# Thrusters.net
KiCad netlist of a schematic drawn in Altium Designer
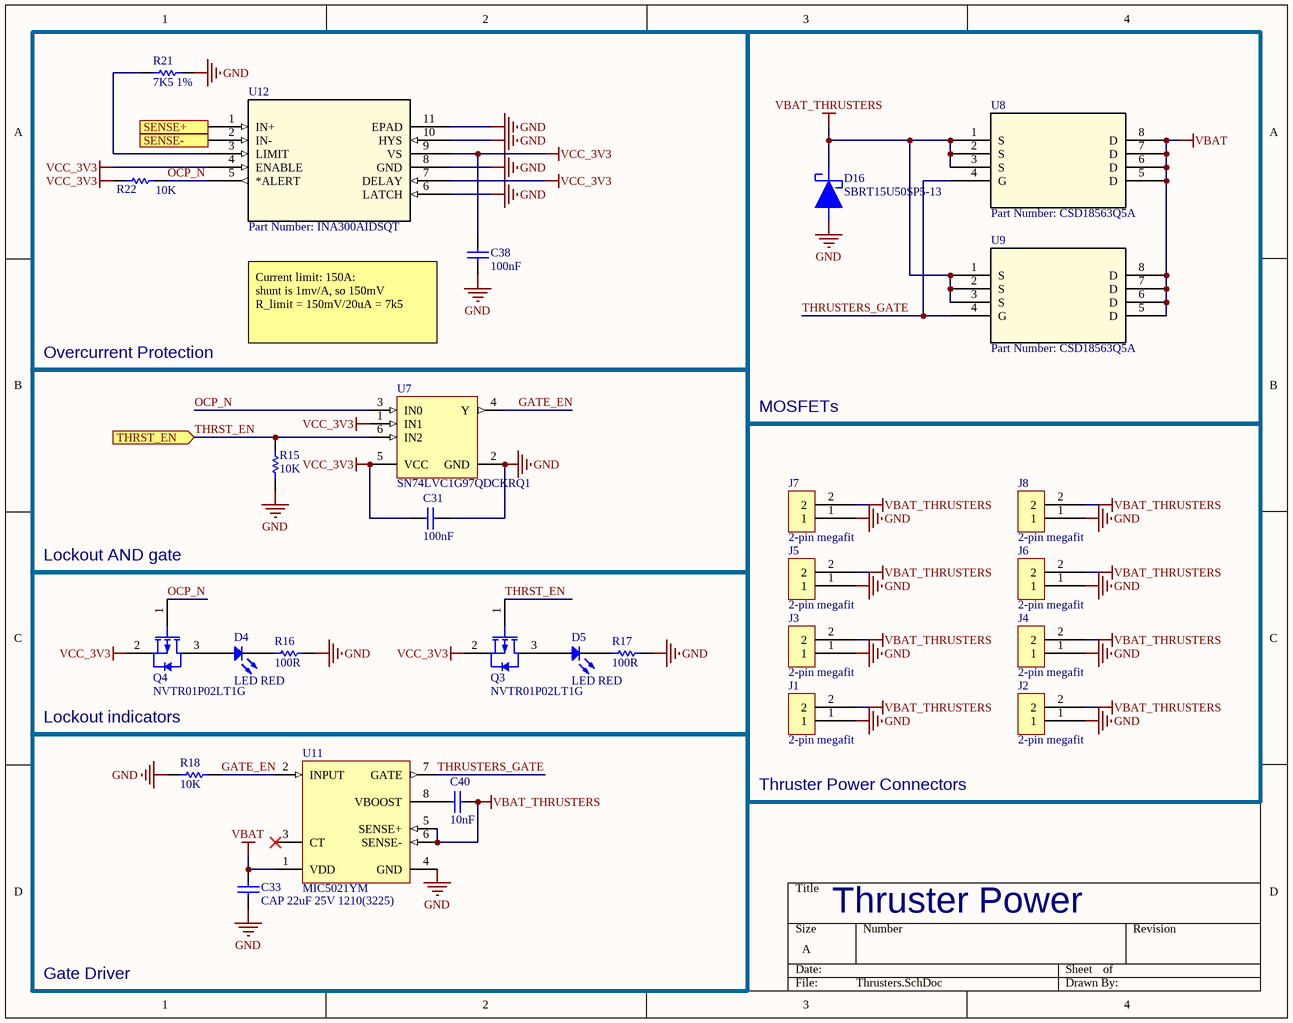
[diagram p0: Thrusters.SchDoc]

(export (version "E")
  (design (tool "Eeschema 10.0.6"))
  (components
    (comp (ref "C31")
      (value "100nF")
      (footprint "CAPC0603(1608)100_N")
      (description "CAP 100nF 10V ±10% 0603 (1608 Metric) Thickness 1mm SMD")
      (fields (field (name "TOLERANCE") "Â±10%"))
      (libsource (lib "Altium Content Vault") (part "CAP"))
    )
    (comp (ref "C33")
      (value "CAP 22uF 25V 1210(3225)")
      (footprint "CAPC1210(3225)220_L")
      (description "CAP 22uF 25V -20% to +80% 1210 (3225 Metric) Thickness 2.2mm SMD")
      (fields (field (name "TOLERANCE") "-20% to +80%"))
      (libsource (lib "Altium Content Vault") (part "CAP"))
    )
    (comp (ref "C38")
      (value "100nF")
      (footprint "CAPC0603(1608)100_N")
      (description "CAP 100nF 10V ±10% 0603 (1608 Metric) Thickness 1mm SMD")
      (fields (field (name "TOLERANCE") "Â±10%"))
      (libsource (lib "Altium Content Vault") (part "CAP"))
    )
    (comp (ref "C40")
      (value "10nF")
      (footprint "CAPC0603(1608)100_L")
      (description "CAP 10nF 25V ±2% 0603 (1608 Metric) Thickness 1mm SMD")
      (fields (field (name "TOLERANCE") "Â±2%"))
      (libsource (lib "Altium Content Vault") (part "CAP"))
    )
    (comp (ref "D4")
      (value "LED RED")
      (footprint "LED_0805")
      (description "led\r\n LTST-C171KRKT")
      (fields
        (field (name "MANUFACTURER") "Lite-On Inc.")
        (field (name "MANUFACTURER PART NUMBER") "LTST-C171KRKT")
      )
      (libsource (lib "CMR_Miscellaneous_Devices") (part "LED0"))
    )
    (comp (ref "D5")
      (value "LED RED")
      (footprint "LED_0805")
      (description "led\r\n LTST-C171KRKT")
      (fields
        (field (name "MANUFACTURER") "Lite-On Inc.")
        (field (name "MANUFACTURER PART NUMBER") "LTST-C171KRKT")
      )
      (libsource (lib "CMR_Miscellaneous_Devices") (part "LED0"))
    )
    (comp (ref "D16")
      (value "SBRT15U50SP5-13")
      (footprint "SBRT15U50SP5-13")
      (fields (field (name "MANUFACTURER") "Diodes Incorporated"))
      (libsource (lib "CMR_Miscellaneous_Devices") (part "SBRT15U50SP5-13"))
    )
    (comp (ref "J1")
      (value "2-pin megafit")
      (footprint "2-pin Megafit RA")
      (libsource (lib "Tauv-Lib") (part "2-pin megafit"))
    )
    (comp (ref "J2")
      (value "2-pin megafit")
      (footprint "2-pin Megafit RA")
      (libsource (lib "Tauv-Lib") (part "2-pin megafit"))
    )
    (comp (ref "J3")
      (value "2-pin megafit")
      (footprint "2-pin Megafit RA")
      (libsource (lib "Tauv-Lib") (part "2-pin megafit"))
    )
    (comp (ref "J4")
      (value "2-pin megafit")
      (footprint "2-pin Megafit RA")
      (libsource (lib "Tauv-Lib") (part "2-pin megafit"))
    )
    (comp (ref "J5")
      (value "2-pin megafit")
      (footprint "2-pin Megafit RA")
      (libsource (lib "Tauv-Lib") (part "2-pin megafit"))
    )
    (comp (ref "J6")
      (value "2-pin megafit")
      (footprint "2-pin Megafit RA")
      (libsource (lib "Tauv-Lib") (part "2-pin megafit"))
    )
    (comp (ref "J7")
      (value "2-pin megafit")
      (footprint "2-pin Megafit RA")
      (libsource (lib "Tauv-Lib") (part "2-pin megafit"))
    )
    (comp (ref "J8")
      (value "2-pin megafit")
      (footprint "2-pin Megafit RA")
      (libsource (lib "Tauv-Lib") (part "2-pin megafit"))
    )
    (comp (ref "Q3")
      (value "NVTR01P02LT1G")
      (footprint "ONSC-SOT-23-3-318-08_V")
      (description "Power MOSFET, -20 V, -1.3 A, P-Channel, 3-Pin SOT-23, Pb-Free, Tape and Reel")
      (fields (field (name "MANUFACTURER") "On Semiconductor"))
      (libsource (lib "Altium Content Vault") (part "ONSC-PMOS-G1S2D3-3_D"))
    )
    (comp (ref "Q4")
      (value "NVTR01P02LT1G")
      (footprint "ONSC-SOT-23-3-318-08_V")
      (description "Power MOSFET, -20 V, -1.3 A, P-Channel, 3-Pin SOT-23, Pb-Free, Tape and Reel")
      (fields (field (name "MANUFACTURER") "On Semiconductor"))
      (libsource (lib "Altium Content Vault") (part "ONSC-PMOS-G1S2D3-3_D"))
    )
    (comp (ref "R15")
      (value "10K")
      (footprint "RESC0603(1608)_N")
      (description "10K 0.1W 5% 0603 (1608 Metric)  SMD")
      (fields (field (name "TOLERANCE") "5 %") (field (name "POWER") "0.1 W"))
      (libsource (lib "Altium Content Vault") (part "RES"))
    )
    (comp (ref "R16")
      (value "100R")
      (footprint "RESC0603(1608)_N")
      (description "100R 0.1W 5% 0603 (1608 Metric)  SMD")
      (fields (field (name "TOLERANCE") "5 %") (field (name "POWER") "0.1 W"))
      (libsource (lib "Altium Content Vault") (part "RES"))
    )
    (comp (ref "R17")
      (value "100R")
      (footprint "RESC0603(1608)_N")
      (description "100R 0.1W 5% 0603 (1608 Metric)  SMD")
      (fields (field (name "TOLERANCE") "5 %") (field (name "POWER") "0.1 W"))
      (libsource (lib "Altium Content Vault") (part "RES"))
    )
    (comp (ref "R18")
      (value "10K")
      (footprint "RESC0603(1608)_N")
      (description "10K 0.1W 5% 0603 (1608 Metric)  SMD")
      (fields (field (name "TOLERANCE") "5 %") (field (name "POWER") "0.1 W"))
      (libsource (lib "Altium Content Vault") (part "RES"))
    )
    (comp (ref "R21")
      (value "7K5 1%")
      (footprint "RESC0603(1608)_N")
      (description "7K5 0.1W 1% 0603 (1608 Metric)  SMD")
      (fields (field (name "TOLERANCE") "1 %") (field (name "POWER") "0.1 W"))
      (libsource (lib "Altium Content Vault") (part "RES"))
    )
    (comp (ref "R22")
      (value "10K")
      (footprint "RESC0603(1608)_N")
      (description "10K 0.1W 5% 0603 (1608 Metric)  SMD")
      (fields (field (name "TOLERANCE") "5 %") (field (name "POWER") "0.1 W"))
      (libsource (lib "Altium Content Vault") (part "RES"))
    )
    (comp (ref "U7")
      (value "SN74LVC1G97QDCKRQ1")
      (footprint "DCK0006A_L")
      (description "Automotive Catalog Configurable Multiple-Function Gate, DCK0006A, LARGE T&R")
      (fields
        (field (name "MANUFACTURER") "Texas Instruments")
        (field (name "GENERIC PART NUMBER") "SN74LVC1G97-Q1")
      )
      (libsource (lib "Altium Content Vault") (part "TI-SN74XXX1GXX-6"))
    )
    (comp (ref "U8")
      (value "Part Number: CSD18563Q5A")
      (footprint "DQJ8")
      (description "No Description Available")
      (fields
        (field (name "MANUFACTURER_PART_NUMBER") "CSD18563Q5A")
        (field (name "COPYRIGHT") "Copyright (C) 2018 Accelerated Designs. All rights reserved")
      )
      (libsource (lib "Tauv-Lib") (part "CSD18563Q5A"))
    )
    (comp (ref "U9")
      (value "Part Number: CSD18563Q5A")
      (footprint "DQJ8")
      (description "No Description Available")
      (fields
        (field (name "MANUFACTURER_PART_NUMBER") "CSD18563Q5A")
        (field (name "COPYRIGHT") "Copyright (C) 2018 Accelerated Designs. All rights reserved")
      )
      (libsource (lib "Tauv-Lib") (part "CSD18563Q5A"))
    )
    (comp (ref "U11")
      (value "MIC5021YM")
      (footprint "MICL-SOICN-8LD-PL-1_V")
      (description "High-Speed High-Side MOSFET Driver, 12 to 36 V, -40 to 85 degC, 8-Pin SOIC, RoHS, Tube")
      (libsource (lib "Altium Content Vault") (part "MICL-MIC5021B_YM-8"))
    )
    (comp (ref "U12")
      (value "Part Number: INA300AIDSQT")
      (footprint "DSQ10_P9X1P5")
      (description "No Description Available")
      (fields
        (field (name "MANUFACTURER_PART_NUMBER") "INA300AIDSQT")
        (field (name "COPYRIGHT") "Copyright (C) 2018 Accelerated Designs. All rights reserved")
      )
      (libsource (lib "Tauv-Lib") (part "INA300AIDSQT"))
    )
  )
  (nets
    (net (code "1") (name "/GATE_EN") (class "Default")
      (node (ref "R18") (pin "1") (pinfunction "1_1") (pintype "passive"))
      (node (ref "U11") (pin "2") (pinfunction "INPUT_2") (pintype "input"))
      (node (ref "U7") (pin "4") (pinfunction "Y_4") (pintype "output"))
    )
    (net (code "2") (name "/OCP_N") (class "Default")
      (node (ref "Q4") (pin "1") (pinfunction "G_1") (pintype "passive"))
      (node (ref "R22") (pin "1") (pinfunction "1_1") (pintype "passive"))
      (node (ref "U12") (pin "5") (pinfunction "*ALERT_5") (pintype "output"))
      (node (ref "U7") (pin "3") (pinfunction "IN0_3") (pintype "input"))
    )
    (net (code "3") (name "/SENSE+") (class "Default")
      (node (ref "U12") (pin "1") (pinfunction "IN+_1") (pintype "input"))
    )
    (net (code "4") (name "/SENSE-") (class "Default")
      (node (ref "U12") (pin "2") (pinfunction "IN-_2") (pintype "input"))
    )
    (net (code "5") (name "/THRST_EN") (class "Default")
      (node (ref "Q3") (pin "1") (pinfunction "G_1") (pintype "passive"))
      (node (ref "R15") (pin "1") (pinfunction "1_1") (pintype "passive"))
      (node (ref "U7") (pin "6") (pinfunction "IN2_6") (pintype "input"))
    )
    (net (code "6") (name "/THRUSTERS_GATE") (class "Default")
      (node (ref "U11") (pin "7") (pinfunction "GATE_7") (pintype "output"))
      (node (ref "U8") (pin "4") (pinfunction "G_4") (pintype "passive"))
      (node (ref "U9") (pin "4") (pinfunction "G_4") (pintype "passive"))
    )
    (net (code "7") (name "GND") (class "Default")
      (node (ref "C31") (pin "1") (pinfunction "1_1") (pintype "passive"))
      (node (ref "C33") (pin "1") (pinfunction "1_1") (pintype "passive"))
      (node (ref "C38") (pin "1") (pinfunction "1_1") (pintype "passive"))
      (node (ref "D16") (pin "1") (pinfunction "1_1") (pintype "passive"))
      (node (ref "J1") (pin "1") (pinfunction "1_1") (pintype "passive"))
      (node (ref "J2") (pin "1") (pinfunction "1_1") (pintype "passive"))
      (node (ref "J3") (pin "1") (pinfunction "1_1") (pintype "passive"))
      (node (ref "J4") (pin "1") (pinfunction "1_1") (pintype "passive"))
      (node (ref "J5") (pin "1") (pinfunction "1_1") (pintype "passive"))
      (node (ref "J6") (pin "1") (pinfunction "1_1") (pintype "passive"))
      (node (ref "J7") (pin "1") (pinfunction "1_1") (pintype "passive"))
      (node (ref "J8") (pin "1") (pinfunction "1_1") (pintype "passive"))
      (node (ref "R15") (pin "2") (pinfunction "2_2") (pintype "passive"))
      (node (ref "R16") (pin "2") (pinfunction "2_2") (pintype "passive"))
      (node (ref "R17") (pin "2") (pinfunction "2_2") (pintype "passive"))
      (node (ref "R18") (pin "2") (pinfunction "2_2") (pintype "passive"))
      (node (ref "R21") (pin "2") (pinfunction "2_2") (pintype "passive"))
      (node (ref "U11") (pin "4") (pinfunction "GND_4") (pintype "power_in"))
      (node (ref "U12") (pin "10") (pinfunction "HYS_10") (pintype "input"))
      (node (ref "U12") (pin "11") (pinfunction "EPAD_11") (pintype "passive"))
      (node (ref "U12") (pin "6") (pinfunction "LATCH_6") (pintype "input"))
      (node (ref "U12") (pin "8") (pinfunction "GND_8") (pintype "power_in"))
      (node (ref "U7") (pin "2") (pinfunction "GND_2") (pintype "power_in"))
    )
    (net (code "8") (name "Net-(D4-A)") (class "Default")
      (node (ref "D4") (pin "2") (pinfunction "A_2") (pintype "passive"))
      (node (ref "Q4") (pin "3") (pinfunction "D_3") (pintype "passive"))
    )
    (net (code "9") (name "Net-(D4-K)") (class "Default")
      (node (ref "D4") (pin "1") (pinfunction "K_1") (pintype "passive"))
      (node (ref "R16") (pin "1") (pinfunction "1_1") (pintype "passive"))
    )
    (net (code "10") (name "Net-(D5-A)") (class "Default")
      (node (ref "D5") (pin "2") (pinfunction "A_2") (pintype "passive"))
      (node (ref "Q3") (pin "3") (pinfunction "D_3") (pintype "passive"))
    )
    (net (code "11") (name "Net-(D5-K)") (class "Default")
      (node (ref "D5") (pin "1") (pinfunction "K_1") (pintype "passive"))
      (node (ref "R17") (pin "1") (pinfunction "1_1") (pintype "passive"))
    )
    (net (code "12") (name "Net-(U11-VBOOST)") (class "Default")
      (node (ref "C40") (pin "1") (pinfunction "1_1") (pintype "passive"))
      (node (ref "U11") (pin "8") (pinfunction "VBOOST_8") (pintype "power_in"))
    )
    (net (code "13") (name "Net-(U12-LIMIT)") (class "Default")
      (node (ref "R21") (pin "1") (pinfunction "1_1") (pintype "passive"))
      (node (ref "U12") (pin "3") (pinfunction "LIMIT_3") (pintype "input"))
    )
    (net (code "14") (name "VBAT") (class "Default")
      (node (ref "C33") (pin "2") (pinfunction "2_2") (pintype "passive"))
      (node (ref "U11") (pin "1") (pinfunction "VDD_1") (pintype "power_in"))
      (node (ref "U8") (pin "5") (pinfunction "D_5") (pintype "passive"))
      (node (ref "U8") (pin "6") (pinfunction "D_6") (pintype "passive"))
      (node (ref "U8") (pin "7") (pinfunction "D_7") (pintype "passive"))
      (node (ref "U8") (pin "8") (pinfunction "D_8") (pintype "passive"))
      (node (ref "U9") (pin "5") (pinfunction "D_5") (pintype "passive"))
      (node (ref "U9") (pin "6") (pinfunction "D_6") (pintype "passive"))
      (node (ref "U9") (pin "7") (pinfunction "D_7") (pintype "passive"))
      (node (ref "U9") (pin "8") (pinfunction "D_8") (pintype "passive"))
    )
    (net (code "15") (name "VBAT_THRUSTERS") (class "Default")
      (node (ref "C40") (pin "2") (pinfunction "2_2") (pintype "passive"))
      (node (ref "D16") (pin "2") (pinfunction "2_2") (pintype "passive"))
      (node (ref "J1") (pin "2") (pinfunction "2_2") (pintype "passive"))
      (node (ref "J2") (pin "2") (pinfunction "2_2") (pintype "passive"))
      (node (ref "J3") (pin "2") (pinfunction "2_2") (pintype "passive"))
      (node (ref "J4") (pin "2") (pinfunction "2_2") (pintype "passive"))
      (node (ref "J5") (pin "2") (pinfunction "2_2") (pintype "passive"))
      (node (ref "J6") (pin "2") (pinfunction "2_2") (pintype "passive"))
      (node (ref "J7") (pin "2") (pinfunction "2_2") (pintype "passive"))
      (node (ref "J8") (pin "2") (pinfunction "2_2") (pintype "passive"))
      (node (ref "U11") (pin "5") (pinfunction "SENSE+_5") (pintype "input"))
      (node (ref "U11") (pin "6") (pinfunction "SENSE-_6") (pintype "input"))
      (node (ref "U8") (pin "1") (pinfunction "S_1") (pintype "passive"))
      (node (ref "U8") (pin "2") (pinfunction "S_2") (pintype "passive"))
      (node (ref "U8") (pin "3") (pinfunction "S_3") (pintype "passive"))
      (node (ref "U9") (pin "1") (pinfunction "S_1") (pintype "passive"))
      (node (ref "U9") (pin "2") (pinfunction "S_2") (pintype "passive"))
      (node (ref "U9") (pin "3") (pinfunction "S_3") (pintype "passive"))
    )
    (net (code "16") (name "VCC_3V3") (class "Default")
      (node (ref "C31") (pin "2") (pinfunction "2_2") (pintype "passive"))
      (node (ref "C38") (pin "2") (pinfunction "2_2") (pintype "passive"))
      (node (ref "Q3") (pin "2") (pinfunction "S_2") (pintype "passive"))
      (node (ref "Q4") (pin "2") (pinfunction "S_2") (pintype "passive"))
      (node (ref "R22") (pin "2") (pinfunction "2_2") (pintype "passive"))
      (node (ref "U12") (pin "4") (pinfunction "ENABLE_4") (pintype "input"))
      (node (ref "U12") (pin "7") (pinfunction "DELAY_7") (pintype "input"))
      (node (ref "U12") (pin "9") (pinfunction "VS_9") (pintype "power_in"))
      (node (ref "U7") (pin "1") (pinfunction "IN1_1") (pintype "input"))
      (node (ref "U7") (pin "5") (pinfunction "VCC_5") (pintype "power_in"))
    )
    (net (code "17") (name "unconnected-(U11-CT-Pad3)") (class "Default")
      (node (ref "U11") (pin "3") (pinfunction "CT_3") (pintype "passive+no_connect"))
    )
  )
)
